# openmv2.net
KiCad netlist of a schematic drawn in EAGLE
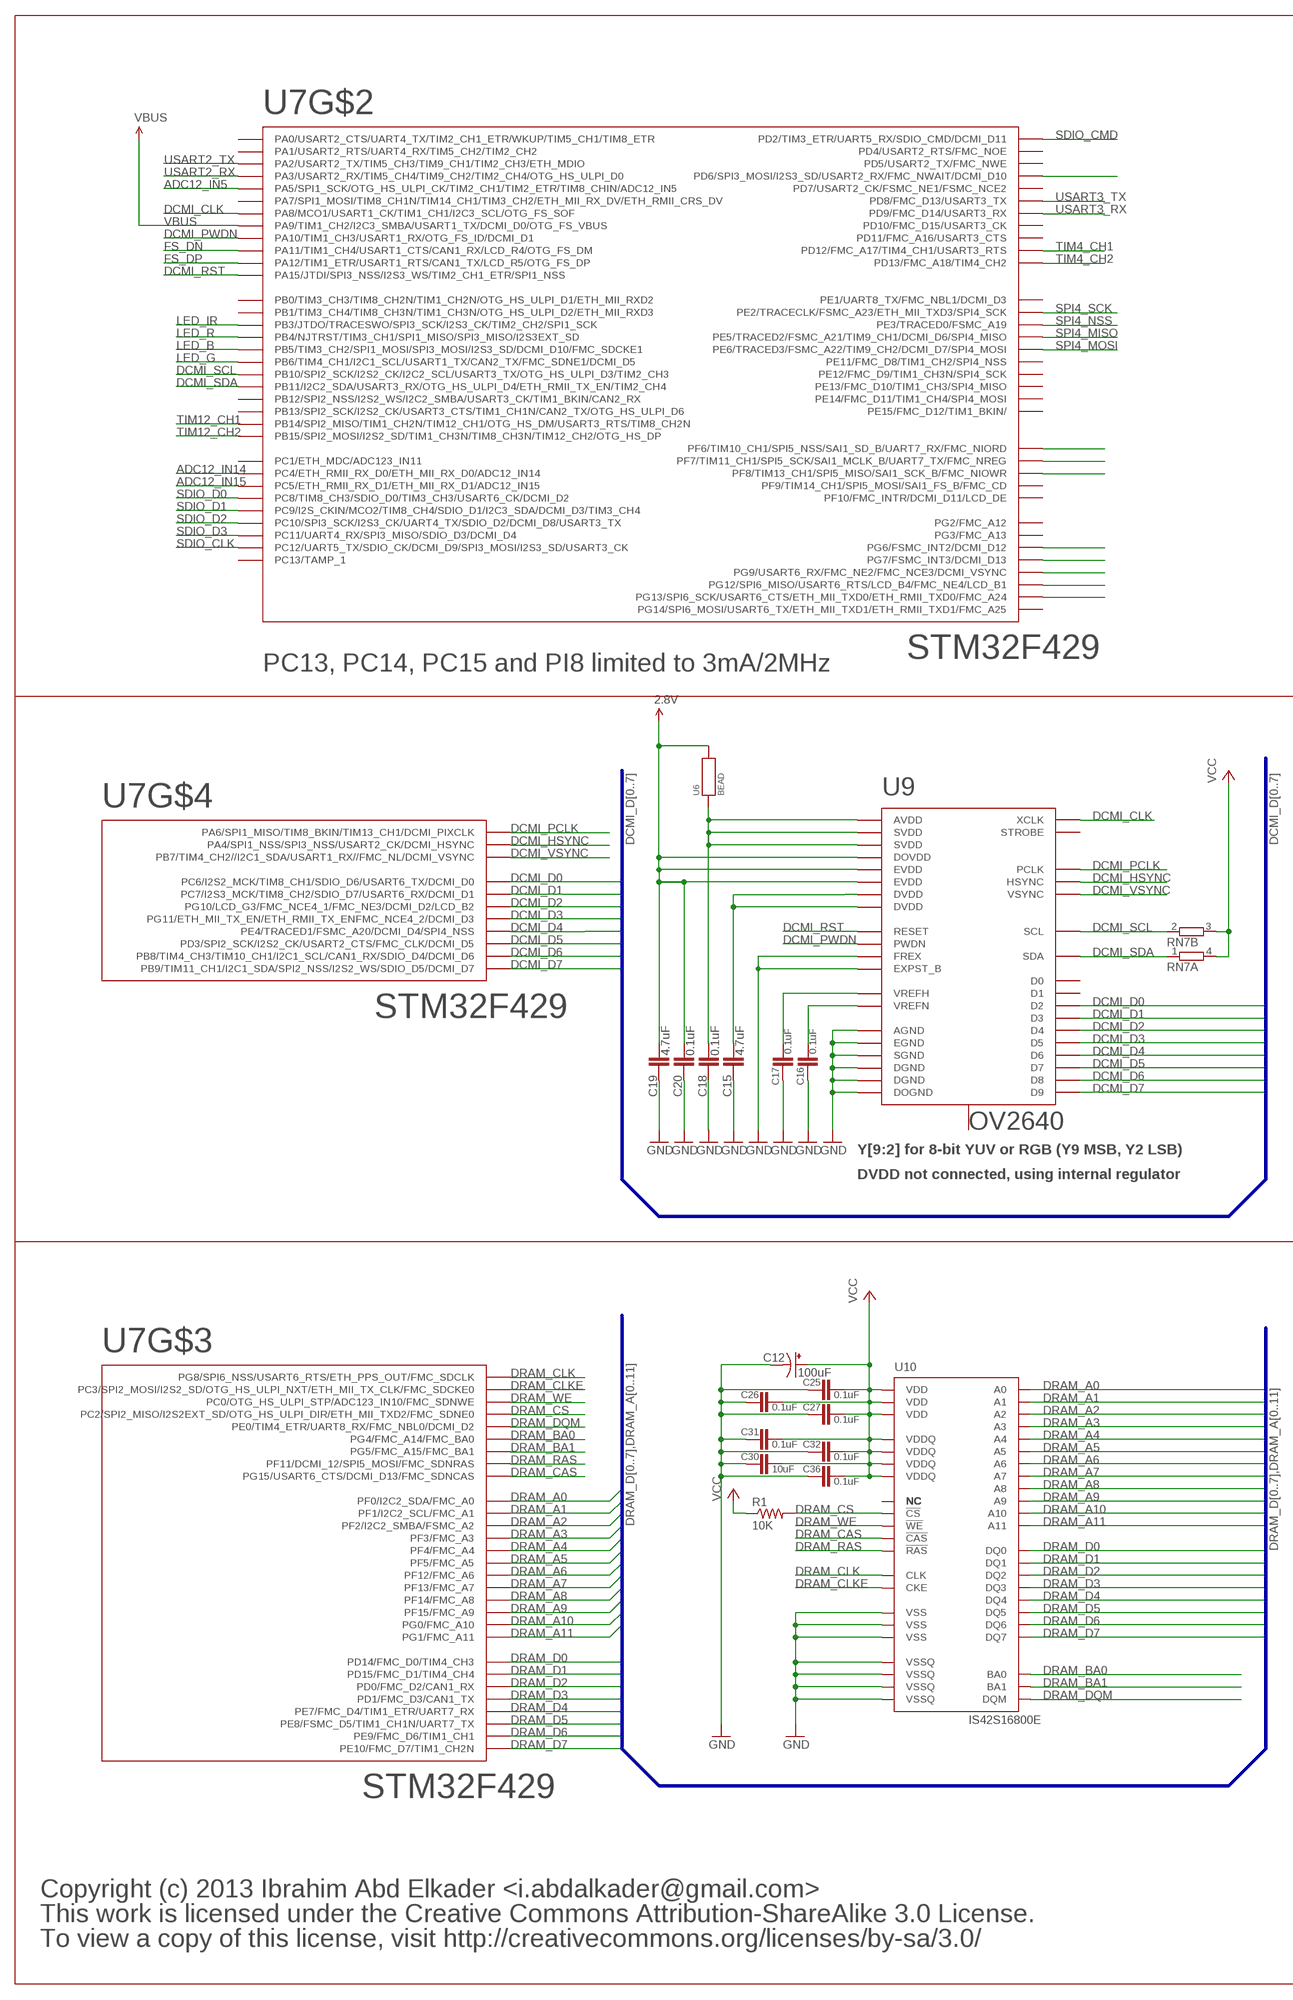
[diagram p0: schematic, sheet 1, part 1 of 2]
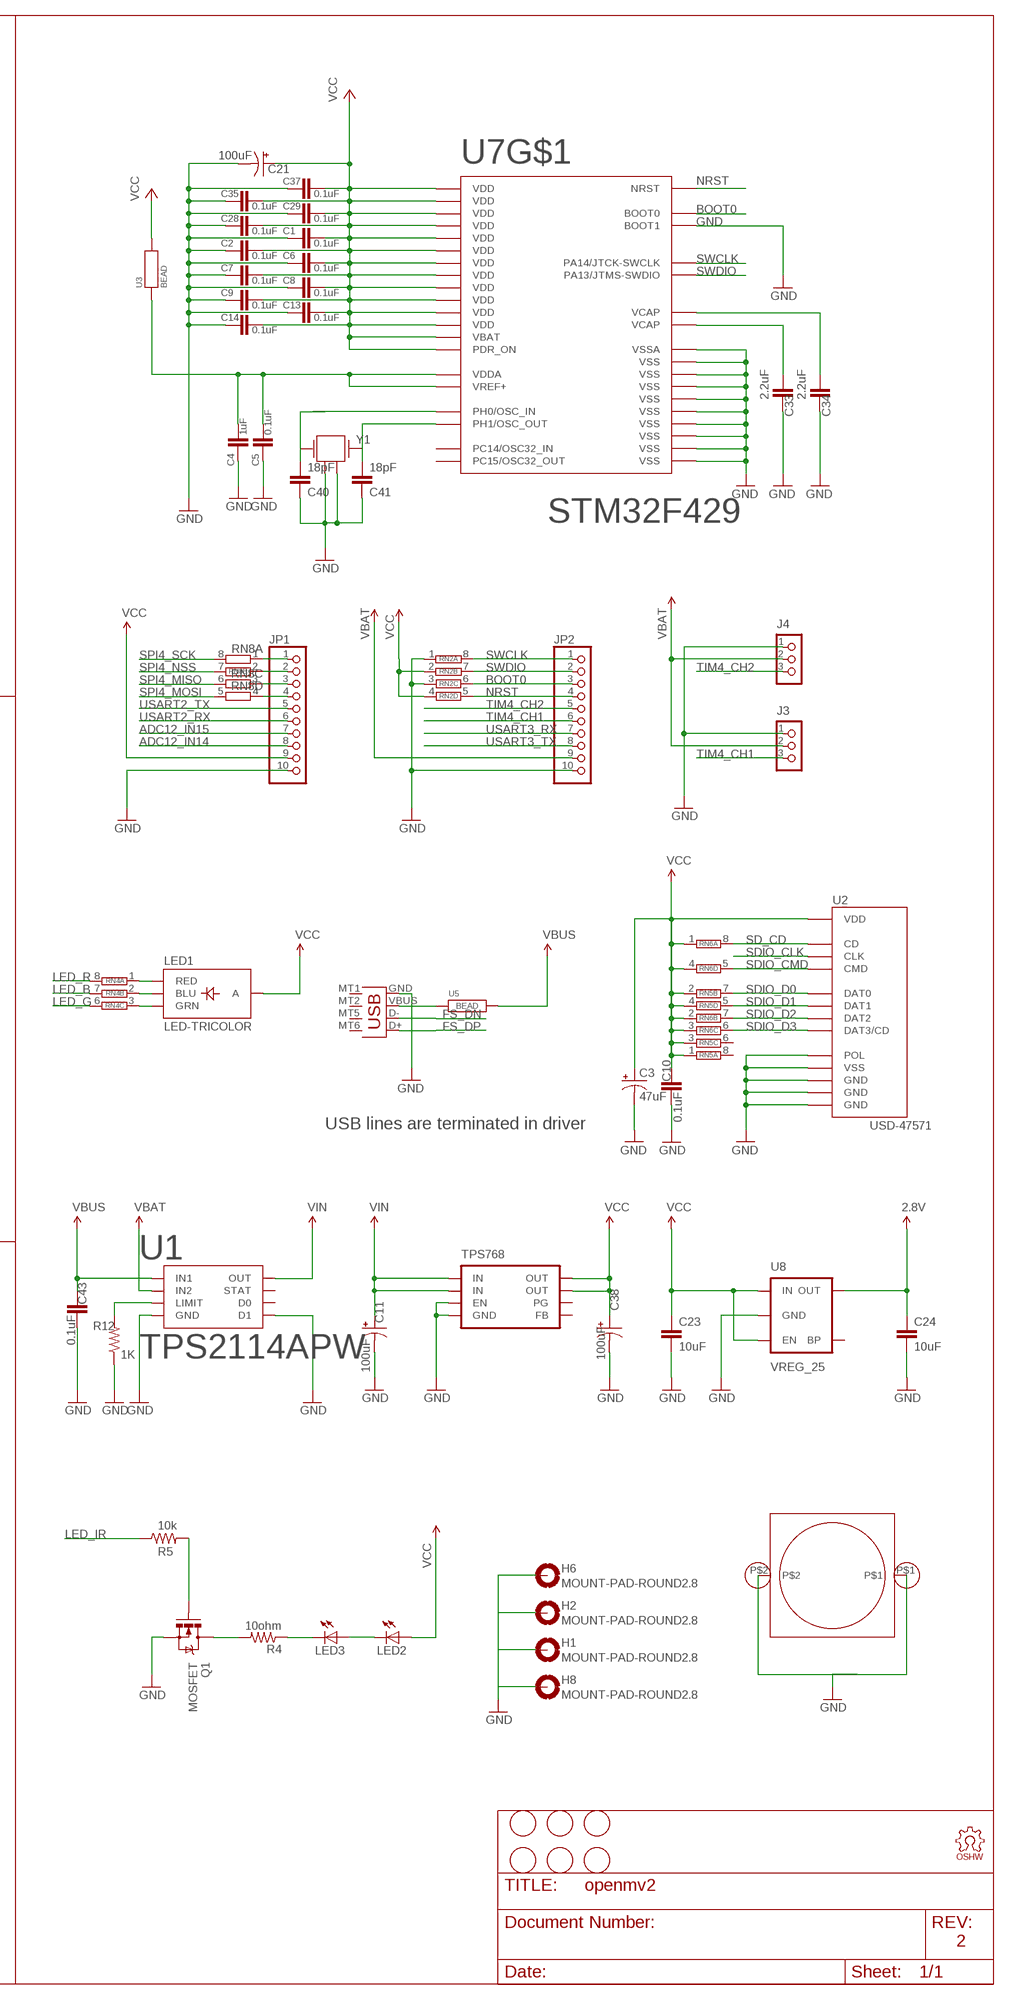
[diagram p1: schematic, sheet 1, part 2 of 2]

(export (version "E")
  (design (tool "Eeschema 10.0.6"))
  (components
    (comp (ref "C1")
      (value "0.1uF")
      (footprint "eagle-import:0402-CAP")
      (libsource (lib "eagle-import") (part "CAP0402-CAP"))
    )
    (comp (ref "C2")
      (value "0.1uF")
      (footprint "eagle-import:0402-CAP")
      (libsource (lib "eagle-import") (part "CAP0402-CAP"))
    )
    (comp (ref "C3")
      (value "47uF")
      (footprint "eagle-import:EIA3216")
      (libsource (lib "eagle-import") (part "CAP_POL1206"))
    )
    (comp (ref "C4")
      (value "1uF")
      (footprint "eagle-import:0402-CAP")
      (libsource (lib "eagle-import") (part "CAP0402-CAP"))
    )
    (comp (ref "C5")
      (value "0.1uF")
      (footprint "eagle-import:0402-CAP")
      (libsource (lib "eagle-import") (part "CAP0402-CAP"))
    )
    (comp (ref "C6")
      (value "0.1uF")
      (footprint "eagle-import:0402-CAP")
      (libsource (lib "eagle-import") (part "CAP0402-CAP"))
    )
    (comp (ref "C7")
      (value "0.1uF")
      (footprint "eagle-import:0402-CAP")
      (libsource (lib "eagle-import") (part "CAP0402-CAP"))
    )
    (comp (ref "C8")
      (value "0.1uF")
      (footprint "eagle-import:0402-CAP")
      (libsource (lib "eagle-import") (part "CAP0402-CAP"))
    )
    (comp (ref "C9")
      (value "0.1uF")
      (footprint "eagle-import:0402-CAP")
      (libsource (lib "eagle-import") (part "CAP0402-CAP"))
    )
    (comp (ref "C10")
      (value "0.1uF")
      (footprint "eagle-import:0402-CAP")
      (libsource (lib "eagle-import") (part "CAP0402-CAP"))
    )
    (comp (ref "C11")
      (value "100uF")
      (footprint "eagle-import:EIA3528")
      (libsource (lib "eagle-import") (part "CAP_POL3528"))
    )
    (comp (ref "C12")
      (value "100uF")
      (footprint "eagle-import:EIA3216")
      (libsource (lib "eagle-import") (part "CAP_POL1206"))
    )
    (comp (ref "C13")
      (value "0.1uF")
      (footprint "eagle-import:0402-CAP")
      (libsource (lib "eagle-import") (part "CAP0402-CAP"))
    )
    (comp (ref "C14")
      (value "0.1uF")
      (footprint "eagle-import:0402-CAP")
      (libsource (lib "eagle-import") (part "CAP0402-CAP"))
    )
    (comp (ref "C15")
      (value "4.7uF")
      (footprint "eagle-import:0402-CAP")
      (libsource (lib "eagle-import") (part "CAP0402-CAP"))
    )
    (comp (ref "C16")
      (value "0.1uF")
      (footprint "eagle-import:0402-CAP")
      (libsource (lib "eagle-import") (part "CAP0402-CAP"))
    )
    (comp (ref "C17")
      (value "0.1uF")
      (footprint "eagle-import:0402-CAP")
      (libsource (lib "eagle-import") (part "CAP0402-CAP"))
    )
    (comp (ref "C18")
      (value "0.1uF")
      (footprint "eagle-import:0402-CAP")
      (libsource (lib "eagle-import") (part "CAP0402-CAP"))
    )
    (comp (ref "C19")
      (value "4.7uF")
      (footprint "eagle-import:0402-CAP")
      (libsource (lib "eagle-import") (part "CAP0402-CAP"))
    )
    (comp (ref "C20")
      (value "0.1uF")
      (footprint "eagle-import:0402-CAP")
      (libsource (lib "eagle-import") (part "CAP0402-CAP"))
    )
    (comp (ref "C21")
      (value "100uF")
      (footprint "eagle-import:EIA3216")
      (libsource (lib "eagle-import") (part "CAP_POL1206"))
    )
    (comp (ref "C23")
      (value "10uF")
      (footprint "eagle-import:0402-CAP")
      (libsource (lib "eagle-import") (part "CAP0402-CAP"))
    )
    (comp (ref "C24")
      (value "10uF")
      (footprint "eagle-import:0402-CAP")
      (libsource (lib "eagle-import") (part "CAP0402-CAP"))
    )
    (comp (ref "C25")
      (value "0.1uF")
      (footprint "eagle-import:0402-CAP")
      (libsource (lib "eagle-import") (part "CAP0402-CAP"))
    )
    (comp (ref "C26")
      (value "0.1uF")
      (footprint "eagle-import:0402-CAP")
      (libsource (lib "eagle-import") (part "CAP0402-CAP"))
    )
    (comp (ref "C27")
      (value "0.1uF")
      (footprint "eagle-import:0402-CAP")
      (libsource (lib "eagle-import") (part "CAP0402-CAP"))
    )
    (comp (ref "C28")
      (value "0.1uF")
      (footprint "eagle-import:0402-CAP")
      (libsource (lib "eagle-import") (part "CAP0402-CAP"))
    )
    (comp (ref "C29")
      (value "0.1uF")
      (footprint "eagle-import:0402-CAP")
      (libsource (lib "eagle-import") (part "CAP0402-CAP"))
    )
    (comp (ref "C30")
      (value "10uF")
      (footprint "eagle-import:0805")
      (libsource (lib "eagle-import") (part "CAP0805"))
    )
    (comp (ref "C31")
      (value "0.1uF")
      (footprint "eagle-import:0402-CAP")
      (libsource (lib "eagle-import") (part "CAP0402-CAP"))
    )
    (comp (ref "C32")
      (value "0.1uF")
      (footprint "eagle-import:0402-CAP")
      (libsource (lib "eagle-import") (part "CAP0402-CAP"))
    )
    (comp (ref "C33")
      (value "2.2uF")
      (footprint "eagle-import:0402-CAP")
      (libsource (lib "eagle-import") (part "CAP0402-CAP"))
    )
    (comp (ref "C34")
      (value "2.2uF")
      (footprint "eagle-import:0402-CAP")
      (libsource (lib "eagle-import") (part "CAP0402-CAP"))
    )
    (comp (ref "C35")
      (value "0.1uF")
      (footprint "eagle-import:0402-CAP")
      (libsource (lib "eagle-import") (part "CAP0402-CAP"))
    )
    (comp (ref "C36")
      (value "0.1uF")
      (footprint "eagle-import:0402-CAP")
      (libsource (lib "eagle-import") (part "CAP0402-CAP"))
    )
    (comp (ref "C37")
      (value "0.1uF")
      (footprint "eagle-import:0402-CAP")
      (libsource (lib "eagle-import") (part "CAP0402-CAP"))
    )
    (comp (ref "C38")
      (value "100uF")
      (footprint "eagle-import:EIA3528")
      (libsource (lib "eagle-import") (part "CAP_POL3528"))
    )
    (comp (ref "C40")
      (value "18pF")
      (footprint "eagle-import:0402-CAP")
      (libsource (lib "eagle-import") (part "CAP0402-CAP"))
    )
    (comp (ref "C41")
      (value "18pF")
      (footprint "eagle-import:0402-CAP")
      (libsource (lib "eagle-import") (part "CAP0402-CAP"))
    )
    (comp (ref "C43")
      (value "0.1uF")
      (footprint "eagle-import:0402-CAP")
      (libsource (lib "eagle-import") (part "CAP0402-CAP"))
    )
    (comp (ref "H1")
      (value "MOUNT-PAD-ROUND2.8")
      (footprint "eagle-import:2,8-PAD")
      (libsource (lib "eagle-import") (part "MOUNT-PAD-ROUND2.8"))
    )
    (comp (ref "H2")
      (value "MOUNT-PAD-ROUND2.8")
      (footprint "eagle-import:2,8-PAD")
      (libsource (lib "eagle-import") (part "MOUNT-PAD-ROUND2.8"))
    )
    (comp (ref "H6")
      (value "MOUNT-PAD-ROUND2.8")
      (footprint "eagle-import:2,8-PAD")
      (libsource (lib "eagle-import") (part "MOUNT-PAD-ROUND2.8"))
    )
    (comp (ref "H8")
      (value "MOUNT-PAD-ROUND2.8")
      (footprint "eagle-import:2,8-PAD")
      (libsource (lib "eagle-import") (part "MOUNT-PAD-ROUND2.8"))
    )
    (comp (ref "J3")
      (value "CON_HEADER_1X03")
      (footprint "eagle-import:M1X3_SMD")
      (libsource (lib "eagle-import") (part "CON_HEADER_1X03"))
    )
    (comp (ref "J4")
      (value "CON_HEADER_1X03")
      (footprint "eagle-import:M1X3_SMD")
      (libsource (lib "eagle-import") (part "CON_HEADER_1X03"))
    )
    (comp (ref "JP1")
      (value "PINHD-1X10")
      (footprint "eagle-import:1X10")
      (libsource (lib "eagle-import") (part "PINHD-1X10"))
    )
    (comp (ref "JP2")
      (value "PINHD-1X10")
      (footprint "eagle-import:1X10")
      (libsource (lib "eagle-import") (part "PINHD-1X10"))
    )
    (comp (ref "LED1")
      (value "LED-TRICOLOR")
      (footprint "eagle-import:LED-TRICOLOR-SMD")
      (libsource (lib "eagle-import") (part "LED-TRICOLOR"))
    )
    (comp (ref "LED2")
      (value "LED3MM")
      (footprint "eagle-import:LED3MM")
      (libsource (lib "eagle-import") (part "LED3MM"))
    )
    (comp (ref "LED3")
      (value "LED3MM")
      (footprint "eagle-import:LED3MM")
      (libsource (lib "eagle-import") (part "LED3MM"))
    )
    (comp (ref "LOGO1")
      (value "OSHW_LOGO_FILLX0200-NT")
      (footprint "eagle-import:OSHW_FILLX200_NOTEXT")
      (libsource (lib "eagle-import") (part "OSHW_LOGO_FILLX0200-NT"))
    )
    (comp (ref "Q1")
      (value "MOSFET")
      (footprint "eagle-import:SOT23-3")
      (libsource (lib "eagle-import") (part "MOSFET-NCHANNELSMD"))
    )
    (comp (ref "R1")
      (value "10K")
      (footprint "eagle-import:0402-RES")
      (libsource (lib "eagle-import") (part "sfe_RESISTOR0402-RES"))
    )
    (comp (ref "R4")
      (value "10ohm")
      (footprint "eagle-import:0402-RES")
      (libsource (lib "eagle-import") (part "RESISTOR0402-RES"))
    )
    (comp (ref "R5")
      (value "10k")
      (footprint "eagle-import:0402-RES")
      (libsource (lib "eagle-import") (part "sfe_RESISTOR0402-RES"))
    )
    (comp (ref "R12")
      (value "1K")
      (footprint "eagle-import:0402-RES")
      (libsource (lib "eagle-import") (part "sfe_RESISTOR0402-RES"))
    )
    (comp (ref "RN2")
      (value "4R-NCAT16")
      (footprint "eagle-import:CAT16")
      (fields (field (name "OC_FARNELL") "unknown") (field (name "OC_NEWARK") "unknown"))
      (libsource (lib "eagle-import") (part "4R-NCAT16"))
    )
    (comp (ref "RN4")
      (value "4R-NCAT16")
      (footprint "eagle-import:CAT16")
      (fields (field (name "OC_FARNELL") "unknown") (field (name "OC_NEWARK") "unknown"))
      (libsource (lib "eagle-import") (part "4R-NCAT16"))
    )
    (comp (ref "RN5")
      (value "4R-NCAT16")
      (footprint "eagle-import:CAT16")
      (fields (field (name "OC_FARNELL") "unknown") (field (name "OC_NEWARK") "unknown"))
      (libsource (lib "eagle-import") (part "4R-NCAT16"))
    )
    (comp (ref "RN6")
      (value "4R-NCAT16")
      (footprint "eagle-import:CAT16")
      (fields (field (name "OC_FARNELL") "unknown") (field (name "OC_NEWARK") "unknown"))
      (libsource (lib "eagle-import") (part "4R-NCAT16"))
    )
    (comp (ref "RN7")
      (value "2R-NEXBV4V")
      (footprint "eagle-import:EXBV4V")
      (libsource (lib "eagle-import") (part "2R-NEXBV4V"))
    )
    (comp (ref "RN8")
      (value "4R-NCAT16")
      (footprint "eagle-import:CAT16")
      (fields (field (name "OC_FARNELL") "unknown") (field (name "OC_NEWARK") "unknown"))
      (libsource (lib "eagle-import") (part "4R-NCAT16"))
    )
    (comp (ref "U$1")
      (value "LENSMOUNT")
      (footprint "eagle-import:LENSMOUNT")
      (libsource (lib "eagle-import") (part "LENSMOUNT"))
    )
    (comp (ref "U$14")
      (value "FIDUCIAL")
      (footprint "eagle-import:FIDUCIAL_1MM")
      (libsource (lib "eagle-import") (part "FIDUCIAL"))
    )
    (comp (ref "U$15")
      (value "FIDUCIAL")
      (footprint "eagle-import:FIDUCIAL_1MM")
      (libsource (lib "eagle-import") (part "FIDUCIAL"))
    )
    (comp (ref "U$16")
      (value "FIDUCIAL")
      (footprint "eagle-import:FIDUCIAL_1MM")
      (libsource (lib "eagle-import") (part "FIDUCIAL"))
    )
    (comp (ref "U$17")
      (value "FIDUCIAL")
      (footprint "eagle-import:FIDUCIAL_1MM")
      (libsource (lib "eagle-import") (part "FIDUCIAL"))
    )
    (comp (ref "U$19")
      (value "FIDUCIAL")
      (footprint "eagle-import:FIDUCIAL_1MM")
      (libsource (lib "eagle-import") (part "FIDUCIAL"))
    )
    (comp (ref "U$20")
      (value "FIDUCIAL")
      (footprint "eagle-import:FIDUCIAL_1MM")
      (libsource (lib "eagle-import") (part "FIDUCIAL"))
    )
    (comp (ref "U1")
      (value "TPS2114APW")
      (footprint "eagle-import:TSSOP8")
      (libsource (lib "eagle-import") (part "TPS2115APW"))
    )
    (comp (ref "U2")
      (value "USD-47571")
      (footprint "eagle-import:USD-47571")
      (libsource (lib "eagle-import") (part "USD-47571"))
    )
    (comp (ref "U3")
      (value "BEAD")
      (footprint "eagle-import:0402-CAP")
      (libsource (lib "eagle-import") (part "BEAD"))
    )
    (comp (ref "U4")
      (value "TPS768")
      (footprint "eagle-import:SOIC8")
      (libsource (lib "eagle-import") (part "TPS768"))
    )
    (comp (ref "U5")
      (value "BEAD")
      (footprint "eagle-import:0402-CAP")
      (libsource (lib "eagle-import") (part "BEAD"))
    )
    (comp (ref "U6")
      (value "BEAD")
      (footprint "eagle-import:0402-CAP")
      (libsource (lib "eagle-import") (part "BEAD"))
    )
    (comp (ref "U7")
      (value "STM32F429")
      (footprint "eagle-import:LQFP144")
      (libsource (lib "eagle-import") (part "STM32F429"))
    )
    (comp (ref "U8")
      (value "VREG_25")
      (footprint "eagle-import:SOT23-5")
      (libsource (lib "eagle-import") (part "V_REG_LDOSMD"))
    )
    (comp (ref "U9")
      (value "OV2640")
      (footprint "eagle-import:CSP2")
      (libsource (lib "eagle-import") (part "OV2640"))
    )
    (comp (ref "U10")
      (value "IS42S16800E")
      (footprint "eagle-import:TSOPII-54")
      (libsource (lib "eagle-import") (part "IS42S16800E"))
    )
    (comp (ref "X1")
      (value "USB-MICROB")
      (footprint "eagle-import:USB-MICROB")
      (libsource (lib "eagle-import") (part "USB-MICROB"))
    )
    (comp (ref "Y1")
      (value "CRYSTAL")
      (footprint "eagle-import:CRYSTAL3.2X2.5")
      (libsource (lib "eagle-import") (part "CRYSTAL"))
    )
  )
  (nets
    (net (code "1") (name "/ADC12_IN5") (class "Default")
      (node (ref "U7") (pin "41") (pinfunction "PA5/SPI1_SCK/OTG_HS_ULPI_CK/TIM2_CH1/TIM2_ETR/TIM8_CHIN/ADC12_IN5_41") (pintype "bidirectional"))
    )
    (net (code "2") (name "/ADC12_IN14") (class "Default")
      (node (ref "JP1") (pin "8") (pinfunction "8_8") (pintype "passive"))
      (node (ref "U7") (pin "44") (pinfunction "PC4/ETH_RMII_RX_D0/ETH_MII_RX_D0/ADC12_IN14_44") (pintype "bidirectional"))
    )
    (net (code "3") (name "/ADC12_IN15") (class "Default")
      (node (ref "JP1") (pin "7") (pinfunction "7_7") (pintype "passive"))
      (node (ref "U7") (pin "45") (pinfunction "PC5/ETH_RMII_RX_D1/ETH_MII_RX_D1/ADC12_IN15_45") (pintype "bidirectional"))
    )
    (net (code "4") (name "/BOOT0") (class "Default")
      (node (ref "JP2") (pin "3") (pinfunction "3_3") (pintype "passive"))
      (node (ref "RN2") (pin "6") (pinfunction "2_6") (pintype "passive"))
      (node (ref "U7") (pin "138") (pinfunction "BOOT0_138") (pintype "bidirectional"))
    )
    (net (code "5") (name "/DCMI_CLK") (class "Default")
      (node (ref "U7") (pin "100") (pinfunction "PA8/MCO1/USART1_CK/TIM1_CH1/I2C3_SCL/OTG_FS_SOF_100") (pintype "bidirectional"))
      (node (ref "U9") (pin "C4") (pinfunction "XCLK_C4") (pintype "bidirectional"))
    )
    (net (code "6") (name "/DCMI_D0") (class "Default")
      (node (ref "U7") (pin "96") (pinfunction "PC6/I2S2_MCK/TIM8_CH1/SDIO_D6/USART6_TX/DCMI_D0_96") (pintype "bidirectional"))
      (node (ref "U9") (pin "F3") (pinfunction "D2_F3") (pintype "bidirectional"))
    )
    (net (code "7") (name "/DCMI_D1") (class "Default")
      (node (ref "U7") (pin "97") (pinfunction "PC7/I2S3_MCK/TIM8_CH2/SDIO_D7/USART6_RX/DCMI_D1_97") (pintype "bidirectional"))
      (node (ref "U9") (pin "G3") (pinfunction "D3_G3") (pintype "bidirectional"))
    )
    (net (code "8") (name "/DCMI_D2") (class "Default")
      (node (ref "U7") (pin "125") (pinfunction "PG10/LCD_G3/FMC_NCE4_1/FMC_NE3/DCMI_D2/LCD_B2_125") (pintype "bidirectional"))
      (node (ref "U9") (pin "F4") (pinfunction "D4_F4") (pintype "bidirectional"))
    )
    (net (code "9") (name "/DCMI_D3") (class "Default")
      (node (ref "U7") (pin "126") (pinfunction "PG11/ETH_MII_TX_EN/ETH_RMII_TX_ENFMC_NCE4_2/DCMI_D3_126") (pintype "bidirectional"))
      (node (ref "U9") (pin "G4") (pinfunction "D5_G4") (pintype "bidirectional"))
    )
    (net (code "10") (name "/DCMI_D4") (class "Default")
      (node (ref "U7") (pin "3") (pinfunction "PE4/TRACED1/FSMC_A20/DCMI_D4/SPI4_NSS_3") (pintype "bidirectional"))
      (node (ref "U9") (pin "E5") (pinfunction "D6_E5") (pintype "bidirectional"))
    )
    (net (code "11") (name "/DCMI_D5") (class "Default")
      (node (ref "U7") (pin "117") (pinfunction "PD3/SPI2_SCK/I2S2_CK/USART2_CTS/FMC_CLK/DCMI_D5_117") (pintype "bidirectional"))
      (node (ref "U9") (pin "G5") (pinfunction "D7_G5") (pintype "bidirectional"))
    )
    (net (code "12") (name "/DCMI_D6") (class "Default")
      (node (ref "U7") (pin "139") (pinfunction "PB8/TIM4_CH3/TIM10_CH1/I2C1_SCL/CAN1_RX/SDIO_D4/DCMI_D6_139") (pintype "bidirectional"))
      (node (ref "U9") (pin "F5") (pinfunction "D8_F5") (pintype "bidirectional"))
    )
    (net (code "13") (name "/DCMI_D7") (class "Default")
      (node (ref "U7") (pin "140") (pinfunction "PB9/TIM11_CH1/I2C1_SDA/SPI2_NSS/I2S2_WS/SDIO_D5/DCMI_D7_140") (pintype "bidirectional"))
      (node (ref "U9") (pin "G6") (pinfunction "D9_G6") (pintype "bidirectional"))
    )
    (net (code "15") (name "/DCMI_HSYNC") (class "Default")
      (node (ref "U7") (pin "40") (pinfunction "PA4/SPI1_NSS/SPI3_NSS/USART2_CK/DCMI_HSYNC_40") (pintype "bidirectional"))
      (node (ref "U9") (pin "C3") (pinfunction "HSYNC_C3") (pintype "bidirectional"))
    )
    (net (code "16") (name "/DCMI_PCLK") (class "Default")
      (node (ref "U7") (pin "42") (pinfunction "PA6/SPI1_MISO/TIM8_BKIN/TIM13_CH1/DCMI_PIXCLK_42") (pintype "bidirectional"))
      (node (ref "U9") (pin "E3") (pinfunction "PCLK_E3") (pintype "bidirectional"))
    )
    (net (code "17") (name "/DCMI_PWDN") (class "Default")
      (node (ref "U7") (pin "102") (pinfunction "PA10/TIM1_CH3/USART1_RX/OTG_FS_ID/DCMI_D1_102") (pintype "bidirectional"))
      (node (ref "U9") (pin "B6") (pinfunction "PWDN_B6") (pintype "bidirectional"))
    )
    (net (code "18") (name "/DCMI_RST") (class "Default")
      (node (ref "U7") (pin "110") (pinfunction "PA15/JTDI/SPI3_NSS/I2S3_WS/TIM2_CH1_ETR/SPI1_NSS_110") (pintype "bidirectional"))
      (node (ref "U9") (pin "C6") (pinfunction "RESET_C6") (pintype "bidirectional"))
    )
    (net (code "19") (name "/DCMI_SCL") (class "Default")
      (node (ref "RN7") (pin "2") (pinfunction "1_2") (pintype "passive"))
      (node (ref "U7") (pin "69") (pinfunction "PB10/SPI2_SCK/I2S2_CK/I2C2_SCL/USART3_TX/OTG_HS_ULPI_D3/TIM2_CH3_69") (pintype "bidirectional"))
      (node (ref "U9") (pin "C2") (pinfunction "SCL_C2") (pintype "bidirectional"))
    )
    (net (code "20") (name "/DCMI_SDA") (class "Default")
      (node (ref "RN7") (pin "1") (pinfunction "1_1") (pintype "passive"))
      (node (ref "U7") (pin "70") (pinfunction "PB11/I2C2_SDA/USART3_RX/OTG_HS_ULPI_D4/ETH_RMII_TX_EN/TIM2_CH4_70") (pintype "bidirectional"))
      (node (ref "U9") (pin "C1") (pinfunction "SDA_C1") (pintype "bidirectional"))
    )
    (net (code "21") (name "/DCMI_VSYNC") (class "Default")
      (node (ref "U7") (pin "137") (pinfunction "PB7/TIM4_CH2//I2C1_SDA/USART1_RX//FMC_NL/DCMI_VSYNC_137") (pintype "bidirectional"))
      (node (ref "U9") (pin "D2") (pinfunction "VSYNC_D2") (pintype "bidirectional"))
    )
    (net (code "22") (name "/DRAM_A0") (class "Default")
      (node (ref "U10") (pin "23") (pinfunction "A0_23") (pintype "input"))
      (node (ref "U7") (pin "10") (pinfunction "PF0/I2C2_SDA/FMC_A0_10") (pintype "bidirectional"))
    )
    (net (code "23") (name "/DRAM_A1") (class "Default")
      (node (ref "U10") (pin "24") (pinfunction "A1_24") (pintype "input"))
      (node (ref "U7") (pin "11") (pinfunction "PF1/I2C2_SCL/FMC_A1_11") (pintype "bidirectional"))
    )
    (net (code "24") (name "/DRAM_A2") (class "Default")
      (node (ref "U10") (pin "25") (pinfunction "A2_25") (pintype "input"))
      (node (ref "U7") (pin "12") (pinfunction "PF2/I2C2_SMBA/FSMC_A2_12") (pintype "bidirectional"))
    )
    (net (code "25") (name "/DRAM_A3") (class "Default")
      (node (ref "U10") (pin "26") (pinfunction "A3_26") (pintype "input"))
      (node (ref "U7") (pin "13") (pinfunction "PF3/FMC_A3_13") (pintype "bidirectional"))
    )
    (net (code "26") (name "/DRAM_A4") (class "Default")
      (node (ref "U10") (pin "29") (pinfunction "A4_29") (pintype "input"))
      (node (ref "U7") (pin "14") (pinfunction "PF4/FMC_A4_14") (pintype "bidirectional"))
    )
    (net (code "27") (name "/DRAM_A5") (class "Default")
      (node (ref "U10") (pin "30") (pinfunction "A5_30") (pintype "input"))
      (node (ref "U7") (pin "15") (pinfunction "PF5/FMC_A5_15") (pintype "bidirectional"))
    )
    (net (code "28") (name "/DRAM_A6") (class "Default")
      (node (ref "U10") (pin "31") (pinfunction "A6_31") (pintype "input"))
      (node (ref "U7") (pin "50") (pinfunction "PF12/FMC_A6_50") (pintype "bidirectional"))
    )
    (net (code "29") (name "/DRAM_A7") (class "Default")
      (node (ref "U10") (pin "32") (pinfunction "A7_32") (pintype "input"))
      (node (ref "U7") (pin "53") (pinfunction "PF13/FMC_A7_53") (pintype "bidirectional"))
    )
    (net (code "30") (name "/DRAM_A8") (class "Default")
      (node (ref "U10") (pin "33") (pinfunction "A8_33") (pintype "input"))
      (node (ref "U7") (pin "54") (pinfunction "PF14/FMC_A8_54") (pintype "bidirectional"))
    )
    (net (code "31") (name "/DRAM_A9") (class "Default")
      (node (ref "U10") (pin "34") (pinfunction "A9_34") (pintype "input"))
      (node (ref "U7") (pin "55") (pinfunction "PF15/FMC_A9_55") (pintype "bidirectional"))
    )
    (net (code "32") (name "/DRAM_A10") (class "Default")
      (node (ref "U10") (pin "22") (pinfunction "A10_22") (pintype "input"))
      (node (ref "U7") (pin "56") (pinfunction "PG0/FMC_A10_56") (pintype "bidirectional"))
    )
    (net (code "33") (name "/DRAM_A11") (class "Default")
      (node (ref "U10") (pin "35") (pinfunction "A11_35") (pintype "input"))
      (node (ref "U7") (pin "57") (pinfunction "PG1/FMC_A11_57") (pintype "bidirectional"))
    )
    (net (code "34") (name "/DRAM_BA0") (class "Default")
      (node (ref "U10") (pin "20") (pinfunction "BA0_20") (pintype "input"))
      (node (ref "U7") (pin "89") (pinfunction "PG4/FMC_A14/FMC_BA0_89") (pintype "bidirectional"))
    )
    (net (code "35") (name "/DRAM_BA1") (class "Default")
      (node (ref "U10") (pin "21") (pinfunction "BA1_21") (pintype "input"))
      (node (ref "U7") (pin "90") (pinfunction "PG5/FMC_A15/FMC_BA1_90") (pintype "bidirectional"))
    )
    (net (code "36") (name "/DRAM_CAS") (class "Default")
      (node (ref "U10") (pin "17") (pinfunction "~{CAS}_17") (pintype "input"))
      (node (ref "U7") (pin "132") (pinfunction "PG15/USART6_CTS/DCMI_D13/FMC_SDNCAS_132") (pintype "bidirectional"))
    )
    (net (code "37") (name "/DRAM_CLK") (class "Default")
      (node (ref "U10") (pin "38") (pinfunction "CLK_38") (pintype "input"))
      (node (ref "U7") (pin "93") (pinfunction "PG8/SPI6_NSS/USART6_RTS/ETH_PPS_OUT/FMC_SDCLK_93") (pintype "bidirectional"))
    )
    (net (code "38") (name "/DRAM_CLKE") (class "Default")
      (node (ref "U10") (pin "37") (pinfunction "CKE_37") (pintype "input"))
      (node (ref "U7") (pin "29") (pinfunction "PC3/SPI2_MOSI/I2S2_SD/OTG_HS_ULPI_NXT/ETH_MII_TX_CLK/FMC_SDCKE0_29") (pintype "bidirectional"))
    )
    (net (code "39") (name "/DRAM_CS") (class "Default")
      (node (ref "R1") (pin "2") (pinfunction "2_2") (pintype "passive"))
      (node (ref "U10") (pin "19") (pinfunction "~{CS}_19") (pintype "input"))
      (node (ref "U7") (pin "28") (pinfunction "PC2/SPI2_MISO/I2S2EXT_SD/OTG_HS_ULPI_DIR/ETH_MII_TXD2/FMC_SDNE0_28") (pintype "bidirectional"))
    )
    (net (code "40") (name "/DRAM_D0") (class "Default")
      (node (ref "U10") (pin "2") (pinfunction "DQ0_2") (pintype "tri_state"))
      (node (ref "U7") (pin "85") (pinfunction "PD14/FMC_D0/TIM4_CH3_85") (pintype "bidirectional"))
    )
    (net (code "41") (name "/DRAM_D1") (class "Default")
      (node (ref "U10") (pin "5") (pinfunction "DQ1_5") (pintype "tri_state"))
      (node (ref "U7") (pin "86") (pinfunction "PD15/FMC_D1/TIM4_CH4_86") (pintype "bidirectional"))
    )
    (net (code "42") (name "/DRAM_D2") (class "Default")
      (node (ref "U10") (pin "8") (pinfunction "DQ2_8") (pintype "tri_state"))
      (node (ref "U7") (pin "114") (pinfunction "PD0/FMC_D2/CAN1_RX_114") (pintype "bidirectional"))
    )
    (net (code "43") (name "/DRAM_D3") (class "Default")
      (node (ref "U10") (pin "11") (pinfunction "DQ3_11") (pintype "tri_state"))
      (node (ref "U7") (pin "115") (pinfunction "PD1/FMC_D3/CAN1_TX_115") (pintype "bidirectional"))
    )
    (net (code "44") (name "/DRAM_D4") (class "Default")
      (node (ref "U10") (pin "44") (pinfunction "DQ4_44") (pintype "tri_state"))
      (node (ref "U7") (pin "58") (pinfunction "PE7/FMC_D4/TIM1_ETR/UART7_RX_58") (pintype "bidirectional"))
    )
    (net (code "45") (name "/DRAM_D5") (class "Default")
      (node (ref "U10") (pin "47") (pinfunction "DQ5_47") (pintype "tri_state"))
      (node (ref "U7") (pin "59") (pinfunction "PE8/FSMC_D5/TIM1_CH1N/UART7_TX_59") (pintype "bidirectional"))
    )
    (net (code "46") (name "/DRAM_D6") (class "Default")
      (node (ref "U10") (pin "50") (pinfunction "DQ6_50") (pintype "tri_state"))
      (node (ref "U7") (pin "60") (pinfunction "PE9/FMC_D6/TIM1_CH1_60") (pintype "bidirectional"))
    )
    (net (code "47") (name "/DRAM_D7") (class "Default")
      (node (ref "U10") (pin "53") (pinfunction "DQ7_53") (pintype "tri_state"))
      (node (ref "U7") (pin "63") (pinfunction "PE10/FMC_D7/TIM1_CH2N_63") (pintype "bidirectional"))
    )
    (net (code "48") (name "/DRAM_DQM") (class "Default")
      (node (ref "U10") (pin "39") (pinfunction "DQM_39") (pintype "input"))
      (node (ref "U7") (pin "141") (pinfunction "PE0/TIM4_ETR/UART8_RX/FMC_NBL0/DCMI_D2_141") (pintype "bidirectional"))
    )
    (net (code "49") (name "/DRAM_RAS") (class "Default")
      (node (ref "U10") (pin "18") (pinfunction "~{RAS}_18") (pintype "input"))
      (node (ref "U7") (pin "49") (pinfunction "PF11/DCMI_12/SPI5_MOSI/FMC_SDNRAS_49") (pintype "bidirectional"))
    )
    (net (code "50") (name "/DRAM_WE") (class "Default")
      (node (ref "U10") (pin "16") (pinfunction "~{WE}_16") (pintype "input"))
      (node (ref "U7") (pin "26") (pinfunction "PC0/OTG_HS_ULPI_STP/ADC123_IN10/FMC_SDNWE_26") (pintype "bidirectional"))
    )
    (net (code "51") (name "/FS_DN") (class "Default")
      (node (ref "U7") (pin "103") (pinfunction "PA11/TIM1_CH4/USART1_CTS/CAN1_RX/LCD_R4/OTG_FS_DM_103") (pintype "bidirectional"))
      (node (ref "X1") (pin "D-") (pinfunction "D-_D-") (pintype "bidirectional"))
    )
    (net (code "52") (name "/FS_DP") (class "Default")
      (node (ref "U7") (pin "104") (pinfunction "PA12/TIM1_ETR/USART1_RTS/CAN1_TX/LCD_R5/OTG_FS_DP_104") (pintype "bidirectional"))
      (node (ref "X1") (pin "D+") (pinfunction "D+_D+") (pintype "bidirectional"))
    )
    (net (code "53") (name "/LED_B") (class "Default")
      (node (ref "RN4") (pin "7") (pinfunction "2_7") (pintype "passive"))
      (node (ref "U7") (pin "135") (pinfunction "PB5/TIM3_CH2/SPI1_MOSI/SPI3_MOSI/I2S3_SD/DCMI_D10/FMC_SDCKE1_135") (pintype "bidirectional"))
    )
    (net (code "54") (name "/LED_G") (class "Default")
      (node (ref "RN4") (pin "6") (pinfunction "2_6") (pintype "passive"))
      (node (ref "U7") (pin "136") (pinfunction "PB6/TIM4_CH1/I2C1_SCL/USART1_TX/CAN2_TX/FMC_SDNE1/DCMI_D5_136") (pintype "bidirectional"))
    )
    (net (code "55") (name "/LED_IR") (class "Default")
      (node (ref "R5") (pin "1") (pinfunction "1_1") (pintype "passive"))
      (node (ref "U7") (pin "133") (pinfunction "PB3/JTDO/TRACESWO/SPI3_SCK/I2S3_CK/TIM2_CH2/SPI1_SCK_133") (pintype "bidirectional"))
    )
    (net (code "56") (name "/LED_R") (class "Default")
      (node (ref "RN4") (pin "8") (pinfunction "2_8") (pintype "passive"))
      (node (ref "U7") (pin "134") (pinfunction "PB4/NJTRST/TIM3_CH1/SPI1_MISO/SPI3_MISO/I2S3EXT_SD_134") (pintype "bidirectional"))
    )
    (net (code "57") (name "/NRST") (class "Default")
      (node (ref "JP2") (pin "4") (pinfunction "4_4") (pintype "passive"))
      (node (ref "RN2") (pin "5") (pinfunction "2_5") (pintype "passive"))
      (node (ref "U7") (pin "25") (pinfunction "NRST_25") (pintype "bidirectional"))
    )
    (net (code "58") (name "/SDIO_CLK") (class "Default")
      (node (ref "U2") (pin "P$5") (pinfunction "CLK_P$5") (pintype "bidirectional"))
      (node (ref "U7") (pin "113") (pinfunction "PC12/UART5_TX/SDIO_CK/DCMI_D9/SPI3_MOSI/I2S3_SD/USART3_CK_113") (pintype "bidirectional"))
    )
    (net (code "59") (name "/SDIO_CMD") (class "Default")
      (node (ref "RN6") (pin "5") (pinfunction "2_5") (pintype "passive"))
      (node (ref "U2") (pin "P$3") (pinfunction "CMD_P$3") (pintype "bidirectional"))
      (node (ref "U7") (pin "116") (pinfunction "PD2/TIM3_ETR/UART5_RX/SDIO_CMD/DCMI_D11_116") (pintype "bidirectional"))
    )
    (net (code "60") (name "/SDIO_D0") (class "Default")
      (node (ref "RN5") (pin "7") (pinfunction "2_7") (pintype "passive"))
      (node (ref "U2") (pin "P$7") (pinfunction "DAT0_P$7") (pintype "bidirectional"))
      (node (ref "U7") (pin "98") (pinfunction "PC8/TIM8_CH3/SDIO_D0/TIM3_CH3/USART6_CK/DCMI_D2_98") (pintype "bidirectional"))
    )
    (net (code "61") (name "/SDIO_D1") (class "Default")
      (node (ref "RN5") (pin "5") (pinfunction "2_5") (pintype "passive"))
      (node (ref "U2") (pin "P$8") (pinfunction "DAT1_P$8") (pintype "bidirectional"))
      (node (ref "U7") (pin "99") (pinfunction "PC9/I2S_CKIN/MCO2/TIM8_CH4/SDIO_D1/I2C3_SDA/DCMI_D3/TIM3_CH4_99") (pintype "bidirectional"))
    )
    (net (code "62") (name "/SDIO_D2") (class "Default")
      (node (ref "RN6") (pin "7") (pinfunction "2_7") (pintype "passive"))
      (node (ref "U2") (pin "P$1") (pinfunction "DAT2_P$1") (pintype "bidirectional"))
      (node (ref "U7") (pin "111") (pinfunction "PC10/SPI3_SCK/I2S3_CK/UART4_TX/SDIO_D2/DCMI_D8/USART3_TX_111") (pintype "bidirectional"))
    )
    (net (code "63") (name "/SDIO_D3") (class "Default")
      (node (ref "RN6") (pin "6") (pinfunction "2_6") (pintype "passive"))
      (node (ref "U2") (pin "P$2") (pinfunction "DAT3/CD_P$2") (pintype "bidirectional"))
      (node (ref "U7") (pin "112") (pinfunction "PC11/UART4_RX/SPI3_MISO/SDIO_D3/DCMI_D4_112") (pintype "bidirectional"))
    )
    (net (code "64") (name "/SD_CD") (class "Default")
      (node (ref "RN6") (pin "8") (pinfunction "2_8") (pintype "passive"))
      (node (ref "U2") (pin "G$5") (pinfunction "CD_G$5") (pintype "power_in"))
      (node (ref "U7") (pin "124") (pinfunction "PG9/USART6_RX/FMC_NE2/FMC_NCE3/DCMI_VSYNC_124") (pintype "bidirectional"))
    )
    (net (code "65") (name "/SPI4_MISO") (class "Default")
      (node (ref "RN8") (pin "6") (pinfunction "2_6") (pintype "passive"))
      (node (ref "U7") (pin "4") (pinfunction "PE5/TRACED2/FSMC_A21/TIM9_CH1/DCMI_D6/SPI4_MISO_4") (pintype "bidirectional"))
    )
    (net (code "66") (name "/SPI4_MOSI") (class "Default")
      (node (ref "RN8") (pin "5") (pinfunction "2_5") (pintype "passive"))
      (node (ref "U7") (pin "5") (pinfunction "PE6/TRACED3/FSMC_A22/TIM9_CH2/DCMI_D7/SPI4_MOSI_5") (pintype "bidirectional"))
    )
    (net (code "67") (name "/SPI4_NSS") (class "Default")
      (node (ref "RN8") (pin "7") (pinfunction "2_7") (pintype "passive"))
      (node (ref "U7") (pin "2") (pinfunction "PE3/TRACED0/FSMC_A19_2") (pintype "bidirectional"))
    )
    (net (code "68") (name "/SPI4_SCK") (class "Default")
      (node (ref "RN8") (pin "8") (pinfunction "2_8") (pintype "passive"))
      (node (ref "U7") (pin "1") (pinfunction "PE2/TRACECLK/FSMC_A23/ETH_MII_TXD3/SPI4_SCK_1") (pintype "bidirectional"))
    )
    (net (code "69") (name "/SWCLK") (class "Default")
      (node (ref "JP2") (pin "1") (pinfunction "1_1") (pintype "passive"))
      (node (ref "RN2") (pin "8") (pinfunction "2_8") (pintype "passive"))
      (node (ref "U7") (pin "109") (pinfunction "PA14/JTCK-SWCLK_109") (pintype "bidirectional"))
    )
    (net (code "70") (name "/SWDIO") (class "Default")
      (node (ref "JP2") (pin "2") (pinfunction "2_2") (pintype "passive"))
      (node (ref "RN2") (pin "7") (pinfunction "2_7") (pintype "passive"))
      (node (ref "U7") (pin "105") (pinfunction "PA13/JTMS-SWDIO_105") (pintype "bidirectional"))
    )
    (net (code "71") (name "/TIM4_CH1") (class "Default")
      (node (ref "J3") (pin "3") (pinfunction "3_3") (pintype "bidirectional"))
      (node (ref "JP2") (pin "6") (pinfunction "6_6") (pintype "passive"))
      (node (ref "U7") (pin "81") (pinfunction "PD12/FMC_A17/TIM4_CH1/USART3_RTS_81") (pintype "bidirectional"))
    )
    (net (code "72") (name "/TIM4_CH2") (class "Default")
      (node (ref "J4") (pin "3") (pinfunction "3_3") (pintype "bidirectional"))
      (node (ref "JP2") (pin "5") (pinfunction "5_5") (pintype "passive"))
      (node (ref "U7") (pin "82") (pinfunction "PD13/FMC_A18/TIM4_CH2_82") (pintype "bidirectional"))
    )
    (net (code "73") (name "/TIM12_CH1") (class "Default")
      (node (ref "U7") (pin "75") (pinfunction "PB14/SPI2_MISO/TIM1_CH2N/TIM12_CH1/OTG_HS_DM/USART3_RTS/TIM8_CH2N_75") (pintype "bidirectional"))
    )
    (net (code "74") (name "/TIM12_CH2") (class "Default")
      (node (ref "U7") (pin "76") (pinfunction "PB15/SPI2_MOSI/I2S2_SD/TIM1_CH3N/TIM8_CH3N/TIM12_CH2/OTG_HS_DP_76") (pintype "bidirectional"))
    )
    (net (code "75") (name "/USART2_RX") (class "Default")
      (node (ref "JP1") (pin "6") (pinfunction "6_6") (pintype "passive"))
      (node (ref "U7") (pin "37") (pinfunction "PA3/USART2_RX/TIM5_CH4/TIM9_CH2/TIM2_CH4/OTG_HS_ULPI_D0_37") (pintype "bidirectional"))
    )
    (net (code "76") (name "/USART2_TX") (class "Default")
      (node (ref "JP1") (pin "5") (pinfunction "5_5") (pintype "passive"))
      (node (ref "U7") (pin "36") (pinfunction "PA2/USART2_TX/TIM5_CH3/TIM9_CH1/TIM2_CH3/ETH_MDIO_36") (pintype "bidirectional"))
    )
    (net (code "77") (name "/USART3_RX") (class "Default")
      (node (ref "JP2") (pin "7") (pinfunction "7_7") (pintype "passive"))
      (node (ref "U7") (pin "78") (pinfunction "PD9/FMC_D14/USART3_RX_78") (pintype "bidirectional"))
    )
    (net (code "78") (name "/USART3_TX") (class "Default")
      (node (ref "JP2") (pin "8") (pinfunction "8_8") (pintype "passive"))
      (node (ref "U7") (pin "77") (pinfunction "PD8/FMC_D13/USART3_TX_77") (pintype "bidirectional"))
    )
    (net (code "80") (name "2.8V") (class "Default")
      (node (ref "C19") (pin "1") (pinfunction "1_1") (pintype "passive"))
      (node (ref "C20") (pin "1") (pinfunction "1_1") (pintype "passive"))
      (node (ref "C24") (pin "1") (pinfunction "1_1") (pintype "passive"))
      (node (ref "U6") (pin "2") (pinfunction "2_2") (pintype "passive"))
      (node (ref "U8") (pin "5") (pinfunction "OUT_5") (pintype "passive"))
      (node (ref "U9") (pin "B1") (pinfunction "DOVDD_B1") (pintype "power_in"))
      (node (ref "U9") (pin "F1") (pinfunction "EVDD_F1") (pintype "power_in"))
      (node (ref "U9") (pin "G1") (pinfunction "EVDD_G1") (pintype "power_in"))
    )
    (net (code "81") (name "GND") (class "Default")
      (node (ref "C1") (pin "2") (pinfunction "2_2") (pintype "passive"))
      (node (ref "C10") (pin "2") (pinfunction "2_2") (pintype "passive"))
      (node (ref "C11") (pin "C") (pinfunction "-_C") (pintype "passive"))
      (node (ref "C12") (pin "C") (pinfunction "-_C") (pintype "passive"))
      (node (ref "C13") (pin "2") (pinfunction "2_2") (pintype "passive"))
      (node (ref "C14") (pin "2") (pinfunction "2_2") (pintype "passive"))
      (node (ref "C15") (pin "2") (pinfunction "2_2") (pintype "passive"))
      (node (ref "C16") (pin "2") (pinfunction "2_2") (pintype "passive"))
      (node (ref "C17") (pin "2") (pinfunction "2_2") (pintype "passive"))
      (node (ref "C18") (pin "2") (pinfunction "2_2") (pintype "passive"))
      (node (ref "C19") (pin "2") (pinfunction "2_2") (pintype "passive"))
      (node (ref "C2") (pin "2") (pinfunction "2_2") (pintype "passive"))
      (node (ref "C20") (pin "2") (pinfunction "2_2") (pintype "passive"))
      (node (ref "C21") (pin "C") (pinfunction "-_C") (pintype "passive"))
      (node (ref "C23") (pin "2") (pinfunction "2_2") (pintype "passive"))
      (node (ref "C24") (pin "2") (pinfunction "2_2") (pintype "passive"))
      (node (ref "C25") (pin "2") (pinfunction "2_2") (pintype "passive"))
      (node (ref "C26") (pin "2") (pinfunction "2_2") (pintype "passive"))
      (node (ref "C27") (pin "2") (pinfunction "2_2") (pintype "passive"))
      (node (ref "C28") (pin "1") (pinfunction "1_1") (pintype "passive"))
      (node (ref "C29") (pin "2") (pinfunction "2_2") (pintype "passive"))
      (node (ref "C3") (pin "C") (pinfunction "-_C") (pintype "passive"))
      (node (ref "C30") (pin "2") (pinfunction "2_2") (pintype "passive"))
      (node (ref "C31") (pin "2") (pinfunction "2_2") (pintype "passive"))
      (node (ref "C32") (pin "2") (pinfunction "2_2") (pintype "passive"))
      (node (ref "C33") (pin "2") (pinfunction "2_2") (pintype "passive"))
      (node (ref "C34") (pin "2") (pinfunction "2_2") (pintype "passive"))
      (node (ref "C35") (pin "2") (pinfunction "2_2") (pintype "passive"))
      (node (ref "C36") (pin "2") (pinfunction "2_2") (pintype "passive"))
      (node (ref "C37") (pin "2") (pinfunction "2_2") (pintype "passive"))
      (node (ref "C38") (pin "C") (pinfunction "-_C") (pintype "passive"))
      (node (ref "C4") (pin "2") (pinfunction "2_2") (pintype "passive"))
      (node (ref "C40") (pin "1") (pinfunction "1_1") (pintype "passive"))
      (node (ref "C41") (pin "1") (pinfunction "1_1") (pintype "passive"))
      (node (ref "C43") (pin "2") (pinfunction "2_2") (pintype "passive"))
      (node (ref "C5") (pin "2") (pinfunction "2_2") (pintype "passive"))
      (node (ref "C6") (pin "2") (pinfunction "2_2") (pintype "passive"))
      (node (ref "C7") (pin "2") (pinfunction "2_2") (pintype "passive"))
      (node (ref "C8") (pin "2") (pinfunction "2_2") (pintype "passive"))
      (node (ref "C9") (pin "2") (pinfunction "2_2") (pintype "passive"))
      (node (ref "H1") (pin "B2,8") (pinfunction "MOUNT_B2,8") (pintype "passive"))
      (node (ref "H2") (pin "B2,8") (pinfunction "MOUNT_B2,8") (pintype "passive"))
      (node (ref "H6") (pin "B2,8") (pinfunction "MOUNT_B2,8") (pintype "passive"))
      (node (ref "H8") (pin "B2,8") (pinfunction "MOUNT_B2,8") (pintype "passive"))
      (node (ref "J3") (pin "1") (pinfunction "1_1") (pintype "bidirectional"))
      (node (ref "J4") (pin "1") (pinfunction "1_1") (pintype "bidirectional"))
      (node (ref "JP1") (pin "10") (pinfunction "10_10") (pintype "passive"))
      (node (ref "JP2") (pin "10") (pinfunction "10_10") (pintype "passive"))
      (node (ref "Q1") (pin "2") (pinfunction "S_2") (pintype "passive"))
      (node (ref "R12") (pin "1") (pinfunction "1_1") (pintype "passive"))
      (node (ref "RN2") (pin "1") (pinfunction "1_1") (pintype "passive"))
      (node (ref "RN2") (pin "3") (pinfunction "1_3") (pintype "passive"))
      (node (ref "U$1") (pin "P$1") (pinfunction "P$1_P$1") (pintype "power_in"))
      (node (ref "U$1") (pin "P$2") (pinfunction "P$2_P$2") (pintype "power_in"))
      (node (ref "U1") (pin "3") (pinfunction "D1_3") (pintype "passive"))
      (node (ref "U1") (pin "5") (pinfunction "GND_5") (pintype "power_in"))
      (node (ref "U10") (pin "12") (pinfunction "VSSQ_12") (pintype "power_in"))
      (node (ref "U10") (pin "28") (pinfunction "VSS_28") (pintype "power_in"))
      (node (ref "U10") (pin "41") (pinfunction "VSS_41") (pintype "power_in"))
      (node (ref "U10") (pin "46") (pinfunction "VSSQ_46") (pintype "power_in"))
      (node (ref "U10") (pin "52") (pinfunction "VSSQ_52") (pintype "power_in"))
      (node (ref "U10") (pin "54") (pinfunction "VSS_54") (pintype "power_in"))
      (node (ref "U10") (pin "6") (pinfunction "VSSQ_6") (pintype "power_in"))
      (node (ref "U2") (pin "G$1") (pinfunction "GND_G$1") (pintype "power_in"))
      (node (ref "U2") (pin "G$2") (pinfunction "GND_G$2") (pintype "power_in"))
      (node (ref "U2") (pin "G$3") (pinfunction "GND_G$3") (pintype "power_in"))
      (node (ref "U2") (pin "G$4") (pinfunction "POL_G$4") (pintype "power_in"))
      (node (ref "U2") (pin "P$6") (pinfunction "VSS_P$6") (pintype "power_in"))
      (node (ref "U4") (pin "1") (pinfunction "GND_1") (pintype "input"))
      (node (ref "U4") (pin "2") (pinfunction "EN_2") (pintype "input"))
      (node (ref "U7") (pin "107") (pinfunction "VSS_107") (pintype "power_in"))
      (node (ref "U7") (pin "120") (pinfunction "VSS_120") (pintype "power_in"))
      (node (ref "U7") (pin "130") (pinfunction "VSS_130") (pintype "power_in"))
      (node (ref "U7") (pin "16") (pinfunction "VSS_16") (pintype "power_in"))
      (node (ref "U7") (pin "31") (pinfunction "VSSA_31") (pintype "power_in"))
      (node (ref "U7") (pin "38") (pinfunction "VSS_38") (pintype "power_in"))
      (node (ref "U7") (pin "48") (pinfunction "BOOT1_48") (pintype "bidirectional"))
      (node (ref "U7") (pin "51") (pinfunction "VSS_51") (pintype "power_in"))
      (node (ref "U7") (pin "61") (pinfunction "VSS_61") (pintype "power_in"))
      (node (ref "U7") (pin "83") (pinfunction "VSS_83") (pintype "power_in"))
      (node (ref "U7") (pin "94") (pinfunction "VSS_94") (pintype "power_in"))
      (node (ref "U8") (pin "2") (pinfunction "GND_2") (pintype "input"))
      (node (ref "U9") (pin "A1") (pinfunction "DOGND_A1") (pintype "power_in"))
      (node (ref "U9") (pin "A2") (pinfunction "EXPST_B_A2") (pintype "output"))
      (node (ref "U9") (pin "A3") (pinfunction "AGND_A3") (pintype "power_in"))
      (node (ref "U9") (pin "A4") (pinfunction "SGND_A4") (pintype "power_in"))
      (node (ref "U9") (pin "B2") (pinfunction "FREX_B2") (pintype "input"))
      (node (ref "U9") (pin "E4") (pinfunction "EGND_E4") (pintype "power_in"))
      (node (ref "U9") (pin "E6") (pinfunction "DGND_E6") (pintype "power_in"))
      (node (ref "U9") (pin "G2") (pinfunction "DGND_G2") (pintype "power_in"))
      (node (ref "X1") (pin "GND") (pinfunction "GND_GND") (pintype "bidirectional"))
      (node (ref "Y1") (pin "2") (pinfunction "P$1_2") (pintype "power_in"))
      (node (ref "Y1") (pin "4") (pinfunction "P$2_4") (pintype "power_in"))
    )
    (net (code "82") (name "Net-(C15-Pad1)") (class "Default")
      (node (ref "C15") (pin "1") (pinfunction "1_1") (pintype "passive"))
      (node (ref "U9") (pin "F2") (pinfunction "DVDD_F2") (pintype "power_in"))
      (node (ref "U9") (pin "F6") (pinfunction "DVDD_F6") (pintype "power_in"))
    )
    (net (code "83") (name "Net-(C33-Pad1)") (class "Default")
      (node (ref "C33") (pin "1") (pinfunction "1_1") (pintype "passive"))
      (node (ref "U7") (pin "106") (pinfunction "VCAP_106") (pintype "power_in"))
    )
    (net (code "84") (name "Net-(C34-Pad1)") (class "Default")
      (node (ref "C34") (pin "1") (pinfunction "1_1") (pintype "passive"))
      (node (ref "U7") (pin "71") (pinfunction "VCAP_71") (pintype "power_in"))
    )
    (net (code "85") (name "Net-(JP1-Pad1)") (class "Default")
      (node (ref "JP1") (pin "1") (pinfunction "1_1") (pintype "passive"))
      (node (ref "RN8") (pin "1") (pinfunction "1_1") (pintype "passive"))
    )
    (net (code "86") (name "Net-(LED1-BLU)") (class "Default")
      (node (ref "LED1") (pin "B") (pinfunction "BLU_B") (pintype "bidirectional"))
      (node (ref "RN4") (pin "2") (pinfunction "1_2") (pintype "passive"))
    )
    (net (code "87") (name "Net-(LED1-GRN)") (class "Default")
      (node (ref "LED1") (pin "G") (pinfunction "GRN_G") (pintype "bidirectional"))
      (node (ref "RN4") (pin "3") (pinfunction "1_3") (pintype "passive"))
    )
    (net (code "88") (name "Net-(LED1-RED)") (class "Default")
      (node (ref "LED1") (pin "R") (pinfunction "RED_R") (pintype "bidirectional"))
      (node (ref "RN4") (pin "1") (pinfunction "1_1") (pintype "passive"))
    )
    (net (code "89") (name "Net-(LED2-C)") (class "Default")
      (node (ref "LED2") (pin "K") (pinfunction "C_K") (pintype "passive"))
      (node (ref "LED3") (pin "A") (pinfunction "A_A") (pintype "passive"))
    )
    (net (code "90") (name "Net-(LED3-C)") (class "Default")
      (node (ref "LED3") (pin "K") (pinfunction "C_K") (pintype "passive"))
      (node (ref "R4") (pin "1") (pinfunction "1_1") (pintype "passive"))
    )
    (net (code "91") (name "Net-(Q1-D)") (class "Default")
      (node (ref "Q1") (pin "3") (pinfunction "D_3") (pintype "passive"))
      (node (ref "R4") (pin "2") (pinfunction "2_2") (pintype "passive"))
    )
    (net (code "92") (name "Net-(Q1-G)") (class "Default")
      (node (ref "Q1") (pin "1") (pinfunction "G_1") (pintype "passive"))
      (node (ref "R5") (pin "2") (pinfunction "2_2") (pintype "passive"))
    )
    (net (code "93") (name "Net-(RN8B-1)") (class "Default")
      (node (ref "JP1") (pin "2") (pinfunction "2_2") (pintype "passive"))
      (node (ref "RN8") (pin "2") (pinfunction "1_2") (pintype "passive"))
    )
    (net (code "94") (name "Net-(RN8C-1)") (class "Default")
      (node (ref "JP1") (pin "3") (pinfunction "3_3") (pintype "passive"))
      (node (ref "RN8") (pin "3") (pinfunction "1_3") (pintype "passive"))
    )
    (net (code "95") (name "Net-(RN8D-1)") (class "Default")
      (node (ref "JP1") (pin "4") (pinfunction "4_4") (pintype "passive"))
      (node (ref "RN8") (pin "4") (pinfunction "1_4") (pintype "passive"))
    )
    (net (code "96") (name "Net-(U1-LIMIT)") (class "Default")
      (node (ref "R12") (pin "2") (pinfunction "2_2") (pintype "passive"))
      (node (ref "U1") (pin "4") (pinfunction "LIMIT_4") (pintype "input"))
    )
    (net (code "97") (name "Net-(U5-Pad1)") (class "Default")
      (node (ref "U5") (pin "1") (pinfunction "1_1") (pintype "passive"))
      (node (ref "X1") (pin "VBUS") (pinfunction "VBUS_VBUS") (pintype "bidirectional"))
    )
    (net (code "98") (name "Net-(U7A-PH0{slash}OSC_IN)") (class "Default")
      (node (ref "C40") (pin "2") (pinfunction "2_2") (pintype "passive"))
      (node (ref "U7") (pin "23") (pinfunction "PH0/OSC_IN_23") (pintype "bidirectional"))
      (node (ref "Y1") (pin "3") (pinfunction "2_3") (pintype "passive"))
    )
    (net (code "99") (name "Net-(U7A-PH1{slash}OSC_OUT)") (class "Default")
      (node (ref "C41") (pin "2") (pinfunction "2_2") (pintype "passive"))
      (node (ref "U7") (pin "24") (pinfunction "PH1/OSC_OUT_24") (pintype "bidirectional"))
      (node (ref "Y1") (pin "1") (pinfunction "1_1") (pintype "passive"))
    )
    (net (code "100") (name "Net-(U7A-VDDA)") (class "Default")
      (node (ref "C4") (pin "1") (pinfunction "1_1") (pintype "passive"))
      (node (ref "C5") (pin "1") (pinfunction "1_1") (pintype "passive"))
      (node (ref "U3") (pin "1") (pinfunction "1_1") (pintype "passive"))
      (node (ref "U7") (pin "32") (pinfunction "VREF+_32") (pintype "power_in"))
      (node (ref "U7") (pin "33") (pinfunction "VDDA_33") (pintype "power_in"))
    )
    (net (code "101") (name "Net-(U9-AVDD)") (class "Default")
      (node (ref "C18") (pin "1") (pinfunction "1_1") (pintype "passive"))
      (node (ref "U6") (pin "1") (pinfunction "1_1") (pintype "passive"))
      (node (ref "U9") (pin "B3") (pinfunction "AVDD_B3") (pintype "power_in"))
      (node (ref "U9") (pin "B4") (pinfunction "SVDD_B4") (pintype "power_in"))
      (node (ref "U9") (pin "B5") (pinfunction "SVDD_B5") (pintype "power_in"))
    )
    (net (code "102") (name "Net-(U9-VREFH)") (class "Default")
      (node (ref "C17") (pin "1") (pinfunction "1_1") (pintype "passive"))
      (node (ref "U9") (pin "C5") (pinfunction "VREFH_C5") (pintype "power_in"))
    )
    (net (code "103") (name "Net-(U9-VREFN)") (class "Default")
      (node (ref "C16") (pin "1") (pinfunction "1_1") (pintype "passive"))
      (node (ref "U9") (pin "A5") (pinfunction "VREFN_A5") (pintype "power_in"))
    )
    (net (code "104") (name "VBAT") (class "Default")
      (node (ref "J3") (pin "2") (pinfunction "2_2") (pintype "bidirectional"))
      (node (ref "J4") (pin "2") (pinfunction "2_2") (pintype "bidirectional"))
      (node (ref "JP2") (pin "9") (pinfunction "9_9") (pintype "passive"))
      (node (ref "U1") (pin "6") (pinfunction "IN2_6") (pintype "power_in"))
    )
    (net (code "105") (name "VBUS") (class "Default")
      (node (ref "C43") (pin "1") (pinfunction "1_1") (pintype "passive"))
      (node (ref "U1") (pin "8") (pinfunction "IN1_8") (pintype "power_in"))
      (node (ref "U5") (pin "2") (pinfunction "2_2") (pintype "passive"))
      (node (ref "U7") (pin "101") (pinfunction "PA9/TIM1_CH2/I2C3_SMBA/USART1_TX/DCMI_D0/OTG_FS_VBUS_101") (pintype "bidirectional"))
    )
    (net (code "106") (name "VCC") (class "Default")
      (node (ref "C1") (pin "1") (pinfunction "1_1") (pintype "passive"))
      (node (ref "C10") (pin "1") (pinfunction "1_1") (pintype "passive"))
      (node (ref "C12") (pin "A") (pinfunction "+_A") (pintype "passive"))
      (node (ref "C13") (pin "1") (pinfunction "1_1") (pintype "passive"))
      (node (ref "C14") (pin "1") (pinfunction "1_1") (pintype "passive"))
      (node (ref "C2") (pin "1") (pinfunction "1_1") (pintype "passive"))
      (node (ref "C21") (pin "A") (pinfunction "+_A") (pintype "passive"))
      (node (ref "C23") (pin "1") (pinfunction "1_1") (pintype "passive"))
      (node (ref "C25") (pin "1") (pinfunction "1_1") (pintype "passive"))
      (node (ref "C26") (pin "1") (pinfunction "1_1") (pintype "passive"))
      (node (ref "C27") (pin "1") (pinfunction "1_1") (pintype "passive"))
      (node (ref "C28") (pin "2") (pinfunction "2_2") (pintype "passive"))
      (node (ref "C29") (pin "1") (pinfunction "1_1") (pintype "passive"))
      (node (ref "C3") (pin "A") (pinfunction "+_A") (pintype "passive"))
      (node (ref "C30") (pin "1") (pinfunction "1_1") (pintype "passive"))
      (node (ref "C31") (pin "1") (pinfunction "1_1") (pintype "passive"))
      (node (ref "C32") (pin "1") (pinfunction "1_1") (pintype "passive"))
      (node (ref "C35") (pin "1") (pinfunction "1_1") (pintype "passive"))
      (node (ref "C36") (pin "1") (pinfunction "1_1") (pintype "passive"))
      (node (ref "C37") (pin "1") (pinfunction "1_1") (pintype "passive"))
      (node (ref "C38") (pin "A") (pinfunction "+_A") (pintype "passive"))
      (node (ref "C6") (pin "1") (pinfunction "1_1") (pintype "passive"))
      (node (ref "C7") (pin "1") (pinfunction "1_1") (pintype "passive"))
      (node (ref "C8") (pin "1") (pinfunction "1_1") (pintype "passive"))
      (node (ref "C9") (pin "1") (pinfunction "1_1") (pintype "passive"))
      (node (ref "JP1") (pin "9") (pinfunction "9_9") (pintype "passive"))
      (node (ref "LED1") (pin "A") (pinfunction "A_A") (pintype "bidirectional"))
      (node (ref "LED2") (pin "A") (pinfunction "A_A") (pintype "passive"))
      (node (ref "R1") (pin "1") (pinfunction "1_1") (pintype "passive"))
      (node (ref "RN2") (pin "2") (pinfunction "1_2") (pintype "passive"))
      (node (ref "RN2") (pin "4") (pinfunction "1_4") (pintype "passive"))
      (node (ref "RN5") (pin "1") (pinfunction "1_1") (pintype "passive"))
      (node (ref "RN5") (pin "2") (pinfunction "1_2") (pintype "passive"))
      (node (ref "RN5") (pin "3") (pinfunction "1_3") (pintype "passive"))
      (node (ref "RN5") (pin "4") (pinfunction "1_4") (pintype "passive"))
      (node (ref "RN6") (pin "1") (pinfunction "1_1") (pintype "passive"))
      (node (ref "RN6") (pin "2") (pinfunction "1_2") (pintype "passive"))
      (node (ref "RN6") (pin "3") (pinfunction "1_3") (pintype "passive"))
      (node (ref "RN6") (pin "4") (pinfunction "1_4") (pintype "passive"))
      (node (ref "RN7") (pin "3") (pinfunction "2_3") (pintype "passive"))
      (node (ref "RN7") (pin "4") (pinfunction "2_4") (pintype "passive"))
      (node (ref "U10") (pin "1") (pinfunction "VDD_1") (pintype "power_in"))
      (node (ref "U10") (pin "14") (pinfunction "VDD_14") (pintype "power_in"))
      (node (ref "U10") (pin "27") (pinfunction "VDD_27") (pintype "power_in"))
      (node (ref "U10") (pin "3") (pinfunction "VDDQ_3") (pintype "power_in"))
      (node (ref "U10") (pin "43") (pinfunction "VDDQ_43") (pintype "power_in"))
      (node (ref "U10") (pin "49") (pinfunction "VDDQ_49") (pintype "power_in"))
      (node (ref "U10") (pin "9") (pinfunction "VDDQ_9") (pintype "power_in"))
      (node (ref "U2") (pin "P$4") (pinfunction "VDD_P$4") (pintype "power_in"))
      (node (ref "U3") (pin "2") (pinfunction "2_2") (pintype "passive"))
      (node (ref "U4") (pin "5") (pinfunction "OUT_5") (pintype "output"))
      (node (ref "U4") (pin "6") (pinfunction "OUT_6") (pintype "output"))
      (node (ref "U7") (pin "108") (pinfunction "VDD_108") (pintype "power_in"))
      (node (ref "U7") (pin "121") (pinfunction "VDD_121") (pintype "power_in"))
      (node (ref "U7") (pin "131") (pinfunction "VDD_131") (pintype "power_in"))
      (node (ref "U7") (pin "143") (pinfunction "PDR_ON_143") (pintype "bidirectional"))
      (node (ref "U7") (pin "144") (pinfunction "VDD_144") (pintype "power_in"))
      (node (ref "U7") (pin "17") (pinfunction "VDD_17") (pintype "power_in"))
      (node (ref "U7") (pin "30") (pinfunction "VDD_30") (pintype "power_in"))
      (node (ref "U7") (pin "39") (pinfunction "VDD_39") (pintype "power_in"))
      (node (ref "U7") (pin "52") (pinfunction "VDD_52") (pintype "power_in"))
      (node (ref "U7") (pin "6") (pinfunction "VBAT_6") (pintype "power_in"))
      (node (ref "U7") (pin "62") (pinfunction "VDD_62") (pintype "power_in"))
      (node (ref "U7") (pin "72") (pinfunction "VDD_72") (pintype "power_in"))
      (node (ref "U7") (pin "84") (pinfunction "VDD_84") (pintype "power_in"))
      (node (ref "U7") (pin "95") (pinfunction "VDD_95") (pintype "power_in"))
      (node (ref "U8") (pin "1") (pinfunction "IN_1") (pintype "input"))
      (node (ref "U8") (pin "3") (pinfunction "EN_3") (pintype "input"))
    )
    (net (code "107") (name "VIN") (class "Default")
      (node (ref "C11") (pin "A") (pinfunction "+_A") (pintype "passive"))
      (node (ref "U1") (pin "7") (pinfunction "OUT_7") (pintype "power_in"))
      (node (ref "U4") (pin "3") (pinfunction "IN_3") (pintype "input"))
      (node (ref "U4") (pin "4") (pinfunction "IN_4") (pintype "input"))
    )
    (net (code "108") (name "unconnected-(RN5A-2-Pad8)") (class "Default")
      (node (ref "RN5") (pin "8") (pinfunction "2_8") (pintype "passive"))
    )
    (net (code "109") (name "unconnected-(RN5C-2-Pad6)") (class "Default")
      (node (ref "RN5") (pin "6") (pinfunction "2_6") (pintype "passive"))
    )
    (net (code "110") (name "unconnected-(U1-D0-Pad2)") (class "Default")
      (node (ref "U1") (pin "2") (pinfunction "D0_2") (pintype "passive"))
    )
    (net (code "111") (name "unconnected-(U1-STAT-Pad1)") (class "Default")
      (node (ref "U1") (pin "1") (pinfunction "STAT_1") (pintype "output"))
    )
    (net (code "112") (name "unconnected-(U4-FB-Pad7)") (class "Default")
      (node (ref "U4") (pin "7") (pinfunction "FB_7") (pintype "bidirectional"))
    )
    (net (code "113") (name "unconnected-(U4-PG-Pad8)") (class "Default")
      (node (ref "U4") (pin "8") (pinfunction "PG_8") (pintype "input"))
    )
    (net (code "114") (name "unconnected-(U7A-PC14{slash}OSC32_IN-Pad8)") (class "Default")
      (node (ref "U7") (pin "8") (pinfunction "PC14/OSC32_IN_8") (pintype "bidirectional"))
    )
    (net (code "115") (name "unconnected-(U7A-PC15{slash}OSC32_OUT-Pad9)") (class "Default")
      (node (ref "U7") (pin "9") (pinfunction "PC15/OSC32_OUT_9") (pintype "bidirectional"))
    )
    (net (code "116") (name "unconnected-(U7B-PA0{slash}USART2_CTS{slash}UART4_TX{slash}TIM2_CH1_ETR{slash}WKUP{slash}TIM5_CH1{slash}TIM8_ETR-Pad34)") (class "Default")
      (node (ref "U7") (pin "34") (pinfunction "PA0/USART2_CTS/UART4_TX/TIM2_CH1_ETR/WKUP/TIM5_CH1/TIM8_ETR_34") (pintype "bidirectional"))
    )
    (net (code "117") (name "unconnected-(U7B-PA1{slash}USART2_RTS{slash}UART4_RX{slash}TIM5_CH2{slash}TIM2_CH2-Pad35)") (class "Default")
      (node (ref "U7") (pin "35") (pinfunction "PA1/USART2_RTS/UART4_RX/TIM5_CH2/TIM2_CH2_35") (pintype "bidirectional"))
    )
    (net (code "118") (name "unconnected-(U7B-PA7{slash}SPI1_MOSI{slash}TIM8_CH1N{slash}TIM14_CH1{slash}TIM3_CH2{slash}ETH_MII_RX_DV{slash}ETH_RMII_CRS_DV-Pad43)") (class "Default")
      (node (ref "U7") (pin "43") (pinfunction "PA7/SPI1_MOSI/TIM8_CH1N/TIM14_CH1/TIM3_CH2/ETH_MII_RX_DV/ETH_RMII_CRS_DV_43") (pintype "bidirectional"))
    )
    (net (code "119") (name "unconnected-(U7B-PB0{slash}TIM3_CH3{slash}TIM8_CH2N{slash}TIM1_CH2N{slash}OTG_HS_ULPI_D1{slash}ETH_MII_RXD2-Pad46)") (class "Default")
      (node (ref "U7") (pin "46") (pinfunction "PB0/TIM3_CH3/TIM8_CH2N/TIM1_CH2N/OTG_HS_ULPI_D1/ETH_MII_RXD2_46") (pintype "bidirectional"))
    )
    (net (code "120") (name "unconnected-(U7B-PB1{slash}TIM3_CH4{slash}TIM8_CH3N{slash}TIM1_CH3N{slash}OTG_HS_ULPI_D2{slash}ETH_MII_RXD3-Pad47)") (class "Default")
      (node (ref "U7") (pin "47") (pinfunction "PB1/TIM3_CH4/TIM8_CH3N/TIM1_CH3N/OTG_HS_ULPI_D2/ETH_MII_RXD3_47") (pintype "bidirectional"))
    )
    (net (code "121") (name "unconnected-(U7B-PB12{slash}SPI2_NSS{slash}I2S2_WS{slash}I2C2_SMBA{slash}USART3_CK{slash}TIM1_BKIN{slash}CAN2_RX-Pad73)") (class "Default")
      (node (ref "U7") (pin "73") (pinfunction "PB12/SPI2_NSS/I2S2_WS/I2C2_SMBA/USART3_CK/TIM1_BKIN/CAN2_RX_73") (pintype "bidirectional"))
    )
    (net (code "122") (name "unconnected-(U7B-PB13{slash}SPI2_SCK{slash}I2S2_CK{slash}USART3_CTS{slash}TIM1_CH1N{slash}CAN2_TX{slash}OTG_HS_ULPI_D6-Pad74)") (class "Default")
      (node (ref "U7") (pin "74") (pinfunction "PB13/SPI2_SCK/I2S2_CK/USART3_CTS/TIM1_CH1N/CAN2_TX/OTG_HS_ULPI_D6_74") (pintype "bidirectional"))
    )
    (net (code "123") (name "unconnected-(U7B-PC1{slash}ETH_MDC{slash}ADC123_IN11-Pad27)") (class "Default")
      (node (ref "U7") (pin "27") (pinfunction "PC1/ETH_MDC/ADC123_IN11_27") (pintype "bidirectional"))
    )
    (net (code "124") (name "unconnected-(U7B-PC13{slash}TAMP_1-Pad7)") (class "Default")
      (node (ref "U7") (pin "7") (pinfunction "PC13/TAMP_1_7") (pintype "bidirectional"))
    )
    (net (code "125") (name "unconnected-(U7B-PD4{slash}USART2_RTS{slash}FMC_NOE-Pad118)") (class "Default")
      (node (ref "U7") (pin "118") (pinfunction "PD4/USART2_RTS/FMC_NOE_118") (pintype "bidirectional"))
    )
    (net (code "126") (name "unconnected-(U7B-PD5{slash}USART2_TX{slash}FMC_NWE-Pad119)") (class "Default")
      (node (ref "U7") (pin "119") (pinfunction "PD5/USART2_TX/FMC_NWE_119") (pintype "bidirectional"))
    )
    (net (code "127") (name "unconnected-(U7B-PD6{slash}SPI3_MOSI{slash}I2S3_SD{slash}USART2_RX{slash}FMC_NWAIT{slash}DCMI_D10-Pad122)") (class "Default")
      (node (ref "U7") (pin "122") (pinfunction "PD6/SPI3_MOSI/I2S3_SD/USART2_RX/FMC_NWAIT/DCMI_D10_122") (pintype "bidirectional"))
    )
    (net (code "128") (name "unconnected-(U7B-PD7{slash}USART2_CK{slash}FSMC_NE1{slash}FSMC_NCE2-Pad123)") (class "Default")
      (node (ref "U7") (pin "123") (pinfunction "PD7/USART2_CK/FSMC_NE1/FSMC_NCE2_123") (pintype "bidirectional"))
    )
    (net (code "129") (name "unconnected-(U7B-PD10{slash}FMC_D15{slash}USART3_CK-Pad79)") (class "Default")
      (node (ref "U7") (pin "79") (pinfunction "PD10/FMC_D15/USART3_CK_79") (pintype "bidirectional"))
    )
    (net (code "130") (name "unconnected-(U7B-PD11{slash}FMC_A16{slash}USART3_CTS-Pad80)") (class "Default")
      (node (ref "U7") (pin "80") (pinfunction "PD11/FMC_A16/USART3_CTS_80") (pintype "bidirectional"))
    )
    (net (code "131") (name "unconnected-(U7B-PE1{slash}UART8_TX{slash}FMC_NBL1{slash}DCMI_D3-Pad142)") (class "Default")
      (node (ref "U7") (pin "142") (pinfunction "PE1/UART8_TX/FMC_NBL1/DCMI_D3_142") (pintype "bidirectional"))
    )
    (net (code "132") (name "unconnected-(U7B-PE11{slash}FMC_D8{slash}TIM1_CH2{slash}SPI4_NSS-Pad64)") (class "Default")
      (node (ref "U7") (pin "64") (pinfunction "PE11/FMC_D8/TIM1_CH2/SPI4_NSS_64") (pintype "bidirectional"))
    )
    (net (code "133") (name "unconnected-(U7B-PE12{slash}FMC_D9{slash}TIM1_CH3N{slash}SPI4_SCK-Pad65)") (class "Default")
      (node (ref "U7") (pin "65") (pinfunction "PE12/FMC_D9/TIM1_CH3N/SPI4_SCK_65") (pintype "bidirectional"))
    )
    (net (code "134") (name "unconnected-(U7B-PE13{slash}FMC_D10{slash}TIM1_CH3{slash}SPI4_MISO-Pad66)") (class "Default")
      (node (ref "U7") (pin "66") (pinfunction "PE13/FMC_D10/TIM1_CH3/SPI4_MISO_66") (pintype "bidirectional"))
    )
    (net (code "135") (name "unconnected-(U7B-PE14{slash}FMC_D11{slash}TIM1_CH4{slash}SPI4_MOSI-Pad67)") (class "Default")
      (node (ref "U7") (pin "67") (pinfunction "PE14/FMC_D11/TIM1_CH4/SPI4_MOSI_67") (pintype "bidirectional"))
    )
    (net (code "136") (name "unconnected-(U7B-PE15{slash}FMC_D12{slash}TIM1_BKIN{slash}-Pad68)") (class "Default")
      (node (ref "U7") (pin "68") (pinfunction "PE15/FMC_D12/TIM1_BKIN/_68") (pintype "bidirectional"))
    )
    (net (code "137") (name "unconnected-(U7B-PF6{slash}TIM10_CH1{slash}SPI5_NSS{slash}SAI1_SD_B{slash}UART7_RX{slash}FMC_NIORD-Pad18)") (class "Default")
      (node (ref "U7") (pin "18") (pinfunction "PF6/TIM10_CH1/SPI5_NSS/SAI1_SD_B/UART7_RX/FMC_NIORD_18") (pintype "bidirectional"))
    )
    (net (code "138") (name "unconnected-(U7B-PF7{slash}TIM11_CH1{slash}SPI5_SCK{slash}SAI1_MCLK_B{slash}UART7_TX{slash}FMC_NREG-Pad19)") (class "Default")
      (node (ref "U7") (pin "19") (pinfunction "PF7/TIM11_CH1/SPI5_SCK/SAI1_MCLK_B/UART7_TX/FMC_NREG_19") (pintype "bidirectional"))
    )
    (net (code "139") (name "unconnected-(U7B-PF8{slash}TIM13_CH1{slash}SPI5_MISO{slash}SAI1_SCK_B{slash}FMC_NIOWR-Pad20)") (class "Default")
      (node (ref "U7") (pin "20") (pinfunction "PF8/TIM13_CH1/SPI5_MISO/SAI1_SCK_B/FMC_NIOWR_20") (pintype "bidirectional"))
    )
    (net (code "140") (name "unconnected-(U7B-PF9{slash}TIM14_CH1{slash}SPI5_MOSI{slash}SAI1_FS_B{slash}FMC_CD-Pad21)") (class "Default")
      (node (ref "U7") (pin "21") (pinfunction "PF9/TIM14_CH1/SPI5_MOSI/SAI1_FS_B/FMC_CD_21") (pintype "bidirectional"))
    )
    (net (code "141") (name "unconnected-(U7B-PF10{slash}FMC_INTR{slash}DCMI_D11{slash}LCD_DE-Pad22)") (class "Default")
      (node (ref "U7") (pin "22") (pinfunction "PF10/FMC_INTR/DCMI_D11/LCD_DE_22") (pintype "bidirectional"))
    )
    (net (code "142") (name "unconnected-(U7B-PG2{slash}FMC_A12-Pad87)") (class "Default")
      (node (ref "U7") (pin "87") (pinfunction "PG2/FMC_A12_87") (pintype "bidirectional"))
    )
    (net (code "143") (name "unconnected-(U7B-PG3{slash}FMC_A13-Pad88)") (class "Default")
      (node (ref "U7") (pin "88") (pinfunction "PG3/FMC_A13_88") (pintype "bidirectional"))
    )
    (net (code "144") (name "unconnected-(U7B-PG6{slash}FSMC_INT2{slash}DCMI_D12-Pad91)") (class "Default")
      (node (ref "U7") (pin "91") (pinfunction "PG6/FSMC_INT2/DCMI_D12_91") (pintype "bidirectional"))
    )
    (net (code "145") (name "unconnected-(U7B-PG7{slash}FSMC_INT3{slash}DCMI_D13-Pad92)") (class "Default")
      (node (ref "U7") (pin "92") (pinfunction "PG7/FSMC_INT3/DCMI_D13_92") (pintype "bidirectional"))
    )
    (net (code "146") (name "unconnected-(U7B-PG12{slash}SPI6_MISO{slash}USART6_RTS{slash}LCD_B4{slash}FMC_NE4{slash}LCD_B1-Pad127)") (class "Default")
      (node (ref "U7") (pin "127") (pinfunction "PG12/SPI6_MISO/USART6_RTS/LCD_B4/FMC_NE4/LCD_B1_127") (pintype "bidirectional"))
    )
    (net (code "147") (name "unconnected-(U7B-PG13{slash}SPI6_SCK{slash}USART6_CTS{slash}ETH_MII_TXD0{slash}ETH_RMII_TXD0{slash}FMC_A24-Pad128)") (class "Default")
      (node (ref "U7") (pin "128") (pinfunction "PG13/SPI6_SCK/USART6_CTS/ETH_MII_TXD0/ETH_RMII_TXD0/FMC_A24_128") (pintype "bidirectional"))
    )
    (net (code "148") (name "unconnected-(U7B-PG14{slash}SPI6_MOSI{slash}USART6_TX{slash}ETH_MII_TXD1{slash}ETH_RMII_TXD1{slash}FMC_A25-Pad129)") (class "Default")
      (node (ref "U7") (pin "129") (pinfunction "PG14/SPI6_MOSI/USART6_TX/ETH_MII_TXD1/ETH_RMII_TXD1/FMC_A25_129") (pintype "bidirectional"))
    )
    (net (code "149") (name "unconnected-(U8-BP-Pad4)") (class "Default")
      (node (ref "U8") (pin "4") (pinfunction "BP_4") (pintype "input"))
    )
    (net (code "150") (name "unconnected-(U9-D0-PadE2)") (class "Default")
      (node (ref "U9") (pin "E2") (pinfunction "D0_E2") (pintype "bidirectional"))
    )
    (net (code "151") (name "unconnected-(U9-D1-PadE1)") (class "Default")
      (node (ref "U9") (pin "E1") (pinfunction "D1_E1") (pintype "bidirectional"))
    )
    (net (code "152") (name "unconnected-(U9-NC-PadD6)") (class "Default")
      (node (ref "U9") (pin "D6") (pinfunction "NC_D6") (pintype "no_connect"))
    )
    (net (code "153") (name "unconnected-(U9-STROBE-PadA6)") (class "Default")
      (node (ref "U9") (pin "A6") (pinfunction "STROBE_A6") (pintype "output"))
    )
    (net (code "154") (name "unconnected-(U10-NC-Pad4)") (class "Default")
      (node (ref "U10") (pin "4") (pinfunction "NC_4") (pintype "no_connect"))
    )
    (net (code "155") (name "unconnected-(U10-NC-Pad7)") (class "Default")
      (node (ref "U10") (pin "7") (pinfunction "NC_7") (pintype "no_connect"))
    )
    (net (code "156") (name "unconnected-(U10-NC-Pad10)") (class "Default")
      (node (ref "U10") (pin "10") (pinfunction "NC_10") (pintype "no_connect"))
    )
    (net (code "157") (name "unconnected-(U10-NC-Pad13)") (class "Default")
      (node (ref "U10") (pin "13") (pinfunction "NC_13") (pintype "no_connect"))
    )
    (net (code "158") (name "unconnected-(U10-NC-Pad15)") (class "Default")
      (node (ref "U10") (pin "15") (pinfunction "NC_15") (pintype "no_connect"))
    )
    (net (code "159") (name "unconnected-(U10-NC-Pad36)") (class "Default")
      (node (ref "U10") (pin "36") (pinfunction "NC_36") (pintype "no_connect"))
    )
    (net (code "160") (name "unconnected-(U10-NC-Pad40)") (class "Default")
      (node (ref "U10") (pin "40") (pinfunction "NC_40") (pintype "no_connect"))
    )
    (net (code "161") (name "unconnected-(U10-NC-Pad42)") (class "Default")
      (node (ref "U10") (pin "42") (pinfunction "NC_42") (pintype "no_connect"))
    )
    (net (code "162") (name "unconnected-(U10-NC-Pad45)") (class "Default")
      (node (ref "U10") (pin "45") (pinfunction "NC_45") (pintype "no_connect"))
    )
    (net (code "163") (name "unconnected-(U10-NC-Pad48)") (class "Default")
      (node (ref "U10") (pin "48") (pinfunction "NC_48") (pintype "no_connect"))
    )
    (net (code "164") (name "unconnected-(U10-NC-Pad51)") (class "Default")
      (node (ref "U10") (pin "51") (pinfunction "NC_51") (pintype "no_connect"))
    )
    (net (code "165") (name "unconnected-(X1-GND1-PadMT1)") (class "Default")
      (node (ref "X1") (pin "MT1") (pinfunction "GND1_MT1") (pintype "passive"))
    )
    (net (code "166") (name "unconnected-(X1-GND2-PadMT2)") (class "Default")
      (node (ref "X1") (pin "MT2") (pinfunction "GND2_MT2") (pintype "passive"))
    )
    (net (code "167") (name "unconnected-(X1-GND3-PadMT5)") (class "Default")
      (node (ref "X1") (pin "MT5") (pinfunction "GND3_MT5") (pintype "passive"))
    )
    (net (code "168") (name "unconnected-(X1-GND4-PadMT6)") (class "Default")
      (node (ref "X1") (pin "MT6") (pinfunction "GND4_MT6") (pintype "passive"))
    )
  )
)
